# Sheet1.net
KiCad netlist of a schematic drawn in Altium Designer
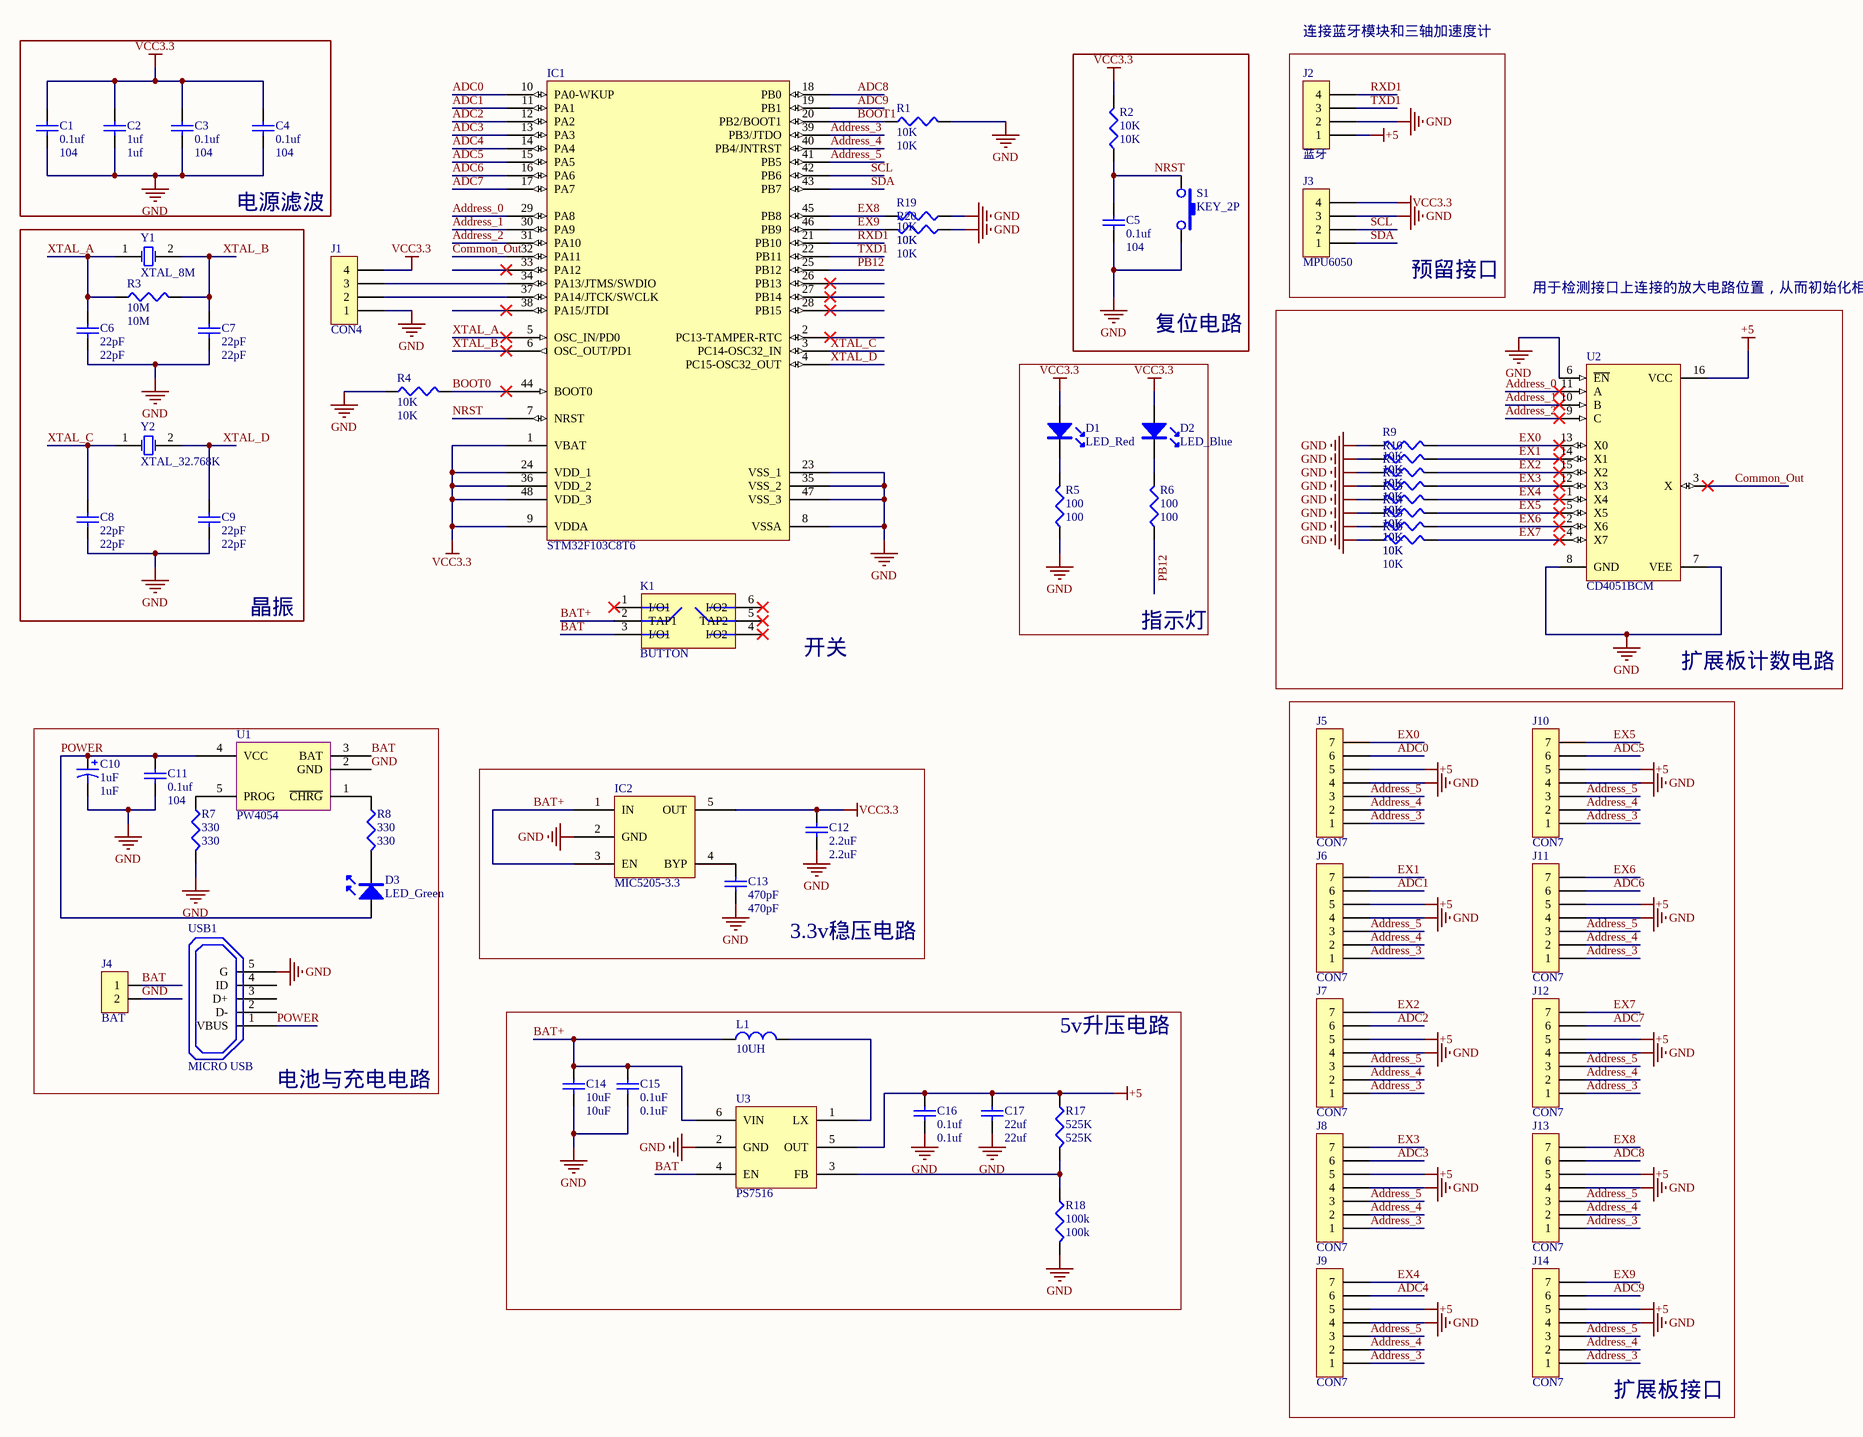
[diagram p0: Sheet1.SchDoc]

(export (version "E")
  (design (tool "Eeschema 10.0.6"))
  (components
    (comp (ref "C1")
      (value "0.1uf")
      (footprint "6-0805_L")
      (description "Capacitor (Semiconductor SIM Model)")
      (fields (field (name "ALTIUM_VALUE") "104") (field (name "PUBLISHER") "Altium Limited"))
      (libsource (lib "Miscellaneous Devices") (part "Cap Semi"))
    )
    (comp (ref "C2")
      (value "1uf")
      (footprint "6-0805_L")
      (description "Capacitor (Semiconductor SIM Model)")
      (fields (field (name "ALTIUM_VALUE") "1uf") (field (name "PUBLISHER") "Altium Limited"))
      (libsource (lib "Miscellaneous Devices") (part "Cap Semi"))
    )
    (comp (ref "C3")
      (value "0.1uf")
      (footprint "6-0805_L")
      (description "Capacitor (Semiconductor SIM Model)")
      (fields (field (name "ALTIUM_VALUE") "104") (field (name "PUBLISHER") "Altium Limited"))
      (libsource (lib "Miscellaneous Devices") (part "Cap Semi"))
    )
    (comp (ref "C4")
      (value "0.1uf")
      (footprint "6-0805_L")
      (description "Capacitor (Semiconductor SIM Model)")
      (fields (field (name "ALTIUM_VALUE") "104") (field (name "PUBLISHER") "Altium Limited"))
      (libsource (lib "Miscellaneous Devices") (part "Cap Semi"))
    )
    (comp (ref "C5")
      (value "0.1uf")
      (footprint "6-0805_L")
      (description "Capacitor (Semiconductor SIM Model)")
      (fields (field (name "ALTIUM_VALUE") "104") (field (name "PUBLISHER") "Altium Limited"))
      (libsource (lib "Miscellaneous Devices") (part "Cap Semi"))
    )
    (comp (ref "C6")
      (value "22pF")
      (footprint "6-0805_L")
      (description "Capacitor (Semiconductor SIM Model)")
      (fields (field (name "ALTIUM_VALUE") "22pF") (field (name "PUBLISHER") "Altium Limited"))
      (libsource (lib "Miscellaneous Devices") (part "Cap Semi"))
    )
    (comp (ref "C7")
      (value "22pF")
      (footprint "6-0805_L")
      (description "Capacitor (Semiconductor SIM Model)")
      (fields (field (name "ALTIUM_VALUE") "22pF") (field (name "PUBLISHER") "Altium Limited"))
      (libsource (lib "Miscellaneous Devices") (part "Cap Semi"))
    )
    (comp (ref "C8")
      (value "22pF")
      (footprint "6-0805_L")
      (description "Capacitor (Semiconductor SIM Model)")
      (fields (field (name "ALTIUM_VALUE") "22pF") (field (name "PUBLISHER") "Altium Limited"))
      (libsource (lib "Miscellaneous Devices") (part "Cap Semi"))
    )
    (comp (ref "C9")
      (value "22pF")
      (footprint "6-0805_L")
      (description "Capacitor (Semiconductor SIM Model)")
      (fields (field (name "ALTIUM_VALUE") "22pF") (field (name "PUBLISHER") "Altium Limited"))
      (libsource (lib "Miscellaneous Devices") (part "Cap Semi"))
    )
    (comp (ref "C10")
      (value "1uF")
      (footprint "C0805")
      (description "Polarized Capacitor (Surface Mount)")
      (fields (field (name "ALTIUM_VALUE") "1uF") (field (name "PUBLISHER") "Altium Limited"))
      (libsource (lib "Miscellaneous Devices") (part "Cap Pol3"))
    )
    (comp (ref "C11")
      (value "0.1uf")
      (footprint "6-0805_L")
      (description "Capacitor (Semiconductor SIM Model)")
      (fields (field (name "ALTIUM_VALUE") "104") (field (name "PUBLISHER") "Altium Limited"))
      (libsource (lib "Miscellaneous Devices") (part "Cap Semi"))
    )
    (comp (ref "C12")
      (value "2.2uF")
      (footprint "6-0805_L")
      (description "Capacitor (Semiconductor SIM Model)")
      (fields (field (name "ALTIUM_VALUE") "2.2uF") (field (name "PUBLISHER") "Altium Limited"))
      (libsource (lib "Miscellaneous Devices") (part "Cap Semi"))
    )
    (comp (ref "C13")
      (value "470pF")
      (footprint "6-0805_L")
      (description "Capacitor (Semiconductor SIM Model)")
      (fields (field (name "ALTIUM_VALUE") "470pF") (field (name "PUBLISHER") "Altium Limited"))
      (libsource (lib "Miscellaneous Devices") (part "Cap Semi"))
    )
    (comp (ref "C14")
      (value "10uF")
      (footprint "6-0805_L")
      (description "Capacitor (Semiconductor SIM Model)")
      (fields (field (name "ALTIUM_VALUE") "10uF") (field (name "PUBLISHER") "Altium Limited"))
      (libsource (lib "Miscellaneous Devices") (part "Cap Semi"))
    )
    (comp (ref "C15")
      (value "0.1uF")
      (footprint "6-0805_L")
      (description "Capacitor (Semiconductor SIM Model)")
      (fields (field (name "ALTIUM_VALUE") "0.1uF") (field (name "PUBLISHER") "Altium Limited"))
      (libsource (lib "Miscellaneous Devices") (part "Cap Semi"))
    )
    (comp (ref "C16")
      (value "0.1uf")
      (footprint "6-0805_L")
      (description "Capacitor (Semiconductor SIM Model)")
      (fields (field (name "ALTIUM_VALUE") "0.1uf") (field (name "PUBLISHER") "Altium Limited"))
      (libsource (lib "Miscellaneous Devices") (part "Cap Semi"))
    )
    (comp (ref "C17")
      (value "22uf")
      (footprint "6-0805_L")
      (description "Capacitor (Semiconductor SIM Model)")
      (fields (field (name "ALTIUM_VALUE") "22uf") (field (name "PUBLISHER") "Altium Limited"))
      (libsource (lib "Miscellaneous Devices") (part "Cap Semi"))
    )
    (comp (ref "D1")
      (value "LED_Red")
      (footprint "6-0805_M")
      (description "LED")
      (libsource (lib "Component") (part "LED"))
    )
    (comp (ref "D2")
      (value "LED_Blue")
      (footprint "6-0805_M")
      (description "LED")
      (libsource (lib "Component") (part "LED"))
    )
    (comp (ref "D3")
      (value "LED_Green")
      (footprint "6-0805_M")
      (description "LED")
      (libsource (lib "Component") (part "LED"))
    )
    (comp (ref "IC1")
      (value "STM32F103C8T6")
      (footprint "LQFP48")
      (description "单片机")
      (fields (field (name "PUBLISHER") "Altium Limited"))
      (libsource (lib "Chip") (part "STM32F103C8T6"))
    )
    (comp (ref "IC2")
      (value "MIC5205-3.3")
      (footprint "SOT-23-5")
      (description "稳压")
      (libsource (lib "Chip") (part "MIC5205-3.3"))
    )
    (comp (ref "J1")
      (value "CON4")
      (footprint "HDR1X4")
      (description "连接器")
      (libsource (lib "Connector") (part "CON4"))
    )
    (comp (ref "J2")
      (value "蓝牙")
      (footprint "HDR1X4")
      (description "Connector")
      (libsource (lib "杂元件库") (part "CON4"))
    )
    (comp (ref "J3")
      (value "MPU6050")
      (footprint "HDR1X4")
      (description "Connector")
      (libsource (lib "杂元件库") (part "CON4"))
    )
    (comp (ref "J4")
      (value "BAT")
      (footprint "HDR1X2")
      (description "Conjunctor")
      (libsource (lib "zj") (part "CON2"))
    )
    (comp (ref "J5")
      (value "CON7")
      (footprint "HDR1X7")
      (description "Connector")
      (libsource (lib "杂元件库") (part "CON7"))
    )
    (comp (ref "J6")
      (value "CON7")
      (footprint "HDR1X7")
      (description "Connector")
      (libsource (lib "杂元件库") (part "CON7"))
    )
    (comp (ref "J7")
      (value "CON7")
      (footprint "HDR1X7")
      (description "Connector")
      (libsource (lib "杂元件库") (part "CON7"))
    )
    (comp (ref "J8")
      (value "CON7")
      (footprint "HDR1X7")
      (description "Connector")
      (libsource (lib "杂元件库") (part "CON7"))
    )
    (comp (ref "J9")
      (value "CON7")
      (footprint "HDR1X7")
      (description "Connector")
      (libsource (lib "杂元件库") (part "CON7"))
    )
    (comp (ref "J10")
      (value "CON7")
      (footprint "HDR1X7")
      (description "Connector")
      (libsource (lib "杂元件库") (part "CON7"))
    )
    (comp (ref "J11")
      (value "CON7")
      (footprint "HDR1X7")
      (description "Connector")
      (libsource (lib "杂元件库") (part "CON7"))
    )
    (comp (ref "J12")
      (value "CON7")
      (footprint "HDR1X7")
      (description "Connector")
      (libsource (lib "杂元件库") (part "CON7"))
    )
    (comp (ref "J13")
      (value "CON7")
      (footprint "HDR1X7")
      (description "Connector")
      (libsource (lib "杂元件库") (part "CON7"))
    )
    (comp (ref "J14")
      (value "CON7")
      (footprint "HDR1X7")
      (description "Connector")
      (libsource (lib "杂元件库") (part "CON7"))
    )
    (comp (ref "K1")
      (value "BUTTON")
      (footprint "My:switch")
      (description "自锁按键")
      (libsource (lib "Component") (part "BUTTON"))
    )
    (comp (ref "L1")
      (value "10UH")
      (footprint "0850")
      (description "电感")
      (libsource (lib "Component") (part "Inductor"))
    )
    (comp (ref "R1")
      (value "10K")
      (footprint "6-0805_L")
      (description "Resistor")
      (fields (field (name "ALTIUM_VALUE") "10K") (field (name "PUBLISHER") "Altium Limited"))
      (libsource (lib "Miscellaneous Devices") (part "Res3"))
    )
    (comp (ref "R2")
      (value "10K")
      (footprint "6-0805_L")
      (description "Resistor")
      (fields (field (name "ALTIUM_VALUE") "10K") (field (name "PUBLISHER") "Altium Limited"))
      (libsource (lib "Miscellaneous Devices") (part "Res3"))
    )
    (comp (ref "R3")
      (value "10M")
      (footprint "6-0805_L")
      (description "Resistor")
      (fields (field (name "ALTIUM_VALUE") "10M") (field (name "PUBLISHER") "Altium Limited"))
      (libsource (lib "Miscellaneous Devices") (part "Res3"))
    )
    (comp (ref "R4")
      (value "10K")
      (footprint "6-0805_L")
      (description "Resistor")
      (fields (field (name "ALTIUM_VALUE") "10K") (field (name "PUBLISHER") "Altium Limited"))
      (libsource (lib "Miscellaneous Devices") (part "Res3"))
    )
    (comp (ref "R5")
      (value "100")
      (footprint "6-0805_L")
      (description "Resistor")
      (fields (field (name "ALTIUM_VALUE") "100") (field (name "PUBLISHER") "Altium Limited"))
      (libsource (lib "Miscellaneous Devices") (part "Res3"))
    )
    (comp (ref "R6")
      (value "100")
      (footprint "6-0805_L")
      (description "Resistor")
      (fields (field (name "ALTIUM_VALUE") "100") (field (name "PUBLISHER") "Altium Limited"))
      (libsource (lib "Miscellaneous Devices") (part "Res3"))
    )
    (comp (ref "R7")
      (value "330")
      (footprint "6-0805_L")
      (description "Resistor")
      (fields (field (name "ALTIUM_VALUE") "330") (field (name "PUBLISHER") "Altium Limited"))
      (libsource (lib "Miscellaneous Devices") (part "Res3"))
    )
    (comp (ref "R8")
      (value "330")
      (footprint "6-0805_L")
      (description "Resistor")
      (fields (field (name "ALTIUM_VALUE") "330") (field (name "PUBLISHER") "Altium Limited"))
      (libsource (lib "Miscellaneous Devices") (part "Res3"))
    )
    (comp (ref "R9")
      (value "10K")
      (footprint "6-0805_L")
      (description "Resistor")
      (fields (field (name "ALTIUM_VALUE") "10K") (field (name "PUBLISHER") "Altium Limited"))
      (libsource (lib "Miscellaneous Devices") (part "Res3"))
    )
    (comp (ref "R10")
      (value "10K")
      (footprint "6-0805_L")
      (description "Resistor")
      (fields (field (name "ALTIUM_VALUE") "10K") (field (name "PUBLISHER") "Altium Limited"))
      (libsource (lib "Miscellaneous Devices") (part "Res3"))
    )
    (comp (ref "R11")
      (value "10K")
      (footprint "6-0805_L")
      (description "Resistor")
      (fields (field (name "ALTIUM_VALUE") "10K") (field (name "PUBLISHER") "Altium Limited"))
      (libsource (lib "Miscellaneous Devices") (part "Res3"))
    )
    (comp (ref "R12")
      (value "10K")
      (footprint "6-0805_L")
      (description "Resistor")
      (fields (field (name "ALTIUM_VALUE") "10K") (field (name "PUBLISHER") "Altium Limited"))
      (libsource (lib "Miscellaneous Devices") (part "Res3"))
    )
    (comp (ref "R13")
      (value "10K")
      (footprint "6-0805_L")
      (description "Resistor")
      (fields (field (name "ALTIUM_VALUE") "10K") (field (name "PUBLISHER") "Altium Limited"))
      (libsource (lib "Miscellaneous Devices") (part "Res3"))
    )
    (comp (ref "R14")
      (value "10K")
      (footprint "6-0805_L")
      (description "Resistor")
      (fields (field (name "ALTIUM_VALUE") "10K") (field (name "PUBLISHER") "Altium Limited"))
      (libsource (lib "Miscellaneous Devices") (part "Res3"))
    )
    (comp (ref "R15")
      (value "10K")
      (footprint "6-0805_L")
      (description "Resistor")
      (fields (field (name "ALTIUM_VALUE") "10K") (field (name "PUBLISHER") "Altium Limited"))
      (libsource (lib "Miscellaneous Devices") (part "Res3"))
    )
    (comp (ref "R16")
      (value "10K")
      (footprint "6-0805_L")
      (description "Resistor")
      (fields (field (name "ALTIUM_VALUE") "10K") (field (name "PUBLISHER") "Altium Limited"))
      (libsource (lib "Miscellaneous Devices") (part "Res3"))
    )
    (comp (ref "R17")
      (value "525K")
      (footprint "6-0805_L")
      (description "Resistor")
      (fields (field (name "ALTIUM_VALUE") "525K") (field (name "PUBLISHER") "Altium Limited"))
      (libsource (lib "Miscellaneous Devices") (part "Res3"))
    )
    (comp (ref "R18")
      (value "100k")
      (footprint "6-0805_L")
      (description "Resistor")
      (fields (field (name "ALTIUM_VALUE") "100k") (field (name "PUBLISHER") "Altium Limited"))
      (libsource (lib "Miscellaneous Devices") (part "Res3"))
    )
    (comp (ref "R19")
      (value "10K")
      (footprint "6-0805_L")
      (description "Resistor")
      (fields (field (name "ALTIUM_VALUE") "10K") (field (name "PUBLISHER") "Altium Limited"))
      (libsource (lib "Miscellaneous Devices") (part "Res3"))
    )
    (comp (ref "R20")
      (value "10K")
      (footprint "6-0805_L")
      (description "Resistor")
      (fields (field (name "ALTIUM_VALUE") "10K") (field (name "PUBLISHER") "Altium Limited"))
      (libsource (lib "Miscellaneous Devices") (part "Res3"))
    )
    (comp (ref "S1")
      (value "KEY_2P")
      (footprint "My:button")
      (description "轻触按键2P")
      (libsource (lib "Component") (part "KEY_2P"))
    )
    (comp (ref "U1") (value "PW4054") (footprint "SOT-23-CT5_L") (libsource (lib "Schlib") (part "PW4054")))
    (comp (ref "U2")
      (value "CD4051BCM")
      (footprint "M16A_N")
      (description "8-Channel Analog Multiplexer/Demultiplexer")
      (fields (field (name "PUBLISHER") "Altium Limited"))
      (libsource (lib "altium-import") (part "root_0_CD4051BCM_"))
    )
    (comp (ref "U3")
      (value "PS7516")
      (footprint "SOT23-6_M")
      (libsource (lib "Integrated_Library1") (part "PS7516"))
    )
    (comp (ref "USB1")
      (value "MICRO USB")
      (footprint "MICRO USB")
      (libsource (lib "Connector") (part "MICRO USB"))
    )
    (comp (ref "Y1")
      (value "XTAL_8M")
      (footprint "xtal")
      (description "Crystal Oscillator")
      (fields (field (name "PUBLISHER") "Altium Limited"))
      (libsource (lib "Miscellaneous Devices") (part "XTAL"))
    )
    (comp (ref "Y2")
      (value "XTAL_32.768K")
      (footprint "R38")
      (description "Crystal Oscillator")
      (fields (field (name "PUBLISHER") "Altium Limited"))
      (libsource (lib "Miscellaneous Devices") (part "XTAL"))
    )
  )
  (nets
    (net (code "1") (name "+5") (class "Default")
      (node (ref "C16") (pin "2") (pinfunction "2_2") (pintype "passive"))
      (node (ref "C17") (pin "2") (pinfunction "2_2") (pintype "passive"))
      (node (ref "J10") (pin "5") (pinfunction "5_5") (pintype "passive"))
      (node (ref "J11") (pin "5") (pinfunction "5_5") (pintype "passive"))
      (node (ref "J12") (pin "5") (pinfunction "5_5") (pintype "passive"))
      (node (ref "J13") (pin "5") (pinfunction "5_5") (pintype "passive"))
      (node (ref "J14") (pin "5") (pinfunction "5_5") (pintype "passive"))
      (node (ref "J2") (pin "1") (pinfunction "1_1") (pintype "passive"))
      (node (ref "J5") (pin "5") (pinfunction "5_5") (pintype "passive"))
      (node (ref "J6") (pin "5") (pinfunction "5_5") (pintype "passive"))
      (node (ref "J7") (pin "5") (pinfunction "5_5") (pintype "passive"))
      (node (ref "J8") (pin "5") (pinfunction "5_5") (pintype "passive"))
      (node (ref "J9") (pin "5") (pinfunction "5_5") (pintype "passive"))
      (node (ref "R17") (pin "1") (pinfunction "1_1") (pintype "passive"))
      (node (ref "U2") (pin "16") (pinfunction "VCC_16") (pintype "power_in"))
      (node (ref "U3") (pin "5") (pinfunction "OUT_5") (pintype "passive"))
    )
    (net (code "2") (name "/ADC0") (class "Default")
      (node (ref "IC1") (pin "10") (pinfunction "PA0-WKUP_10") (pintype "bidirectional"))
      (node (ref "J5") (pin "6") (pinfunction "6_6") (pintype "passive"))
    )
    (net (code "3") (name "/ADC1") (class "Default")
      (node (ref "IC1") (pin "11") (pinfunction "PA1_11") (pintype "bidirectional"))
      (node (ref "J6") (pin "6") (pinfunction "6_6") (pintype "passive"))
    )
    (net (code "4") (name "/ADC2") (class "Default")
      (node (ref "IC1") (pin "12") (pinfunction "PA2_12") (pintype "bidirectional"))
      (node (ref "J7") (pin "6") (pinfunction "6_6") (pintype "passive"))
    )
    (net (code "5") (name "/ADC3") (class "Default")
      (node (ref "IC1") (pin "13") (pinfunction "PA3_13") (pintype "bidirectional"))
      (node (ref "J8") (pin "6") (pinfunction "6_6") (pintype "passive"))
    )
    (net (code "6") (name "/ADC4") (class "Default")
      (node (ref "IC1") (pin "14") (pinfunction "PA4_14") (pintype "bidirectional"))
      (node (ref "J9") (pin "6") (pinfunction "6_6") (pintype "passive"))
    )
    (net (code "7") (name "/ADC5") (class "Default")
      (node (ref "IC1") (pin "15") (pinfunction "PA5_15") (pintype "bidirectional"))
      (node (ref "J10") (pin "6") (pinfunction "6_6") (pintype "passive"))
    )
    (net (code "8") (name "/ADC6") (class "Default")
      (node (ref "IC1") (pin "16") (pinfunction "PA6_16") (pintype "bidirectional"))
      (node (ref "J11") (pin "6") (pinfunction "6_6") (pintype "passive"))
    )
    (net (code "9") (name "/ADC7") (class "Default")
      (node (ref "IC1") (pin "17") (pinfunction "PA7_17") (pintype "bidirectional"))
      (node (ref "J12") (pin "6") (pinfunction "6_6") (pintype "passive"))
    )
    (net (code "10") (name "/ADC8") (class "Default")
      (node (ref "IC1") (pin "18") (pinfunction "PB0_18") (pintype "bidirectional"))
      (node (ref "J13") (pin "6") (pinfunction "6_6") (pintype "passive"))
    )
    (net (code "11") (name "/ADC9") (class "Default")
      (node (ref "IC1") (pin "19") (pinfunction "PB1_19") (pintype "bidirectional"))
      (node (ref "J14") (pin "6") (pinfunction "6_6") (pintype "passive"))
    )
    (net (code "12") (name "/Address_0") (class "Default")
      (node (ref "IC1") (pin "29") (pinfunction "PA8_29") (pintype "bidirectional"))
      (node (ref "U2") (pin "11") (pinfunction "A_11") (pintype "input"))
    )
    (net (code "13") (name "/Address_1") (class "Default")
      (node (ref "IC1") (pin "30") (pinfunction "PA9_30") (pintype "bidirectional"))
      (node (ref "U2") (pin "10") (pinfunction "B_10") (pintype "input"))
    )
    (net (code "14") (name "/Address_2") (class "Default")
      (node (ref "IC1") (pin "31") (pinfunction "PA10_31") (pintype "bidirectional"))
      (node (ref "U2") (pin "9") (pinfunction "C_9") (pintype "input"))
    )
    (net (code "15") (name "/Address_3") (class "Default")
      (node (ref "IC1") (pin "39") (pinfunction "PB3/JTDO_39") (pintype "bidirectional"))
      (node (ref "J10") (pin "1") (pinfunction "1_1") (pintype "passive"))
      (node (ref "J11") (pin "1") (pinfunction "1_1") (pintype "passive"))
      (node (ref "J12") (pin "1") (pinfunction "1_1") (pintype "passive"))
      (node (ref "J13") (pin "1") (pinfunction "1_1") (pintype "passive"))
      (node (ref "J14") (pin "1") (pinfunction "1_1") (pintype "passive"))
      (node (ref "J5") (pin "1") (pinfunction "1_1") (pintype "passive"))
      (node (ref "J6") (pin "1") (pinfunction "1_1") (pintype "passive"))
      (node (ref "J7") (pin "1") (pinfunction "1_1") (pintype "passive"))
      (node (ref "J8") (pin "1") (pinfunction "1_1") (pintype "passive"))
      (node (ref "J9") (pin "1") (pinfunction "1_1") (pintype "passive"))
    )
    (net (code "16") (name "/Address_4") (class "Default")
      (node (ref "IC1") (pin "40") (pinfunction "PB4/JNTRST_40") (pintype "bidirectional"))
      (node (ref "J10") (pin "2") (pinfunction "2_2") (pintype "passive"))
      (node (ref "J11") (pin "2") (pinfunction "2_2") (pintype "passive"))
      (node (ref "J12") (pin "2") (pinfunction "2_2") (pintype "passive"))
      (node (ref "J13") (pin "2") (pinfunction "2_2") (pintype "passive"))
      (node (ref "J14") (pin "2") (pinfunction "2_2") (pintype "passive"))
      (node (ref "J5") (pin "2") (pinfunction "2_2") (pintype "passive"))
      (node (ref "J6") (pin "2") (pinfunction "2_2") (pintype "passive"))
      (node (ref "J7") (pin "2") (pinfunction "2_2") (pintype "passive"))
      (node (ref "J8") (pin "2") (pinfunction "2_2") (pintype "passive"))
      (node (ref "J9") (pin "2") (pinfunction "2_2") (pintype "passive"))
    )
    (net (code "17") (name "/Address_5") (class "Default")
      (node (ref "IC1") (pin "41") (pinfunction "PB5_41") (pintype "bidirectional"))
      (node (ref "J10") (pin "3") (pinfunction "3_3") (pintype "passive"))
      (node (ref "J11") (pin "3") (pinfunction "3_3") (pintype "passive"))
      (node (ref "J12") (pin "3") (pinfunction "3_3") (pintype "passive"))
      (node (ref "J13") (pin "3") (pinfunction "3_3") (pintype "passive"))
      (node (ref "J14") (pin "3") (pinfunction "3_3") (pintype "passive"))
      (node (ref "J5") (pin "3") (pinfunction "3_3") (pintype "passive"))
      (node (ref "J6") (pin "3") (pinfunction "3_3") (pintype "passive"))
      (node (ref "J7") (pin "3") (pinfunction "3_3") (pintype "passive"))
      (node (ref "J8") (pin "3") (pinfunction "3_3") (pintype "passive"))
      (node (ref "J9") (pin "3") (pinfunction "3_3") (pintype "passive"))
    )
    (net (code "18") (name "/BAT") (class "Default")
      (node (ref "J4") (pin "1") (pinfunction "1_1") (pintype "passive"))
      (node (ref "K1") (pin "3") (pinfunction "I/O1_3") (pintype "passive"))
      (node (ref "U1") (pin "3") (pinfunction "BAT_3") (pintype "passive"))
      (node (ref "U3") (pin "4") (pinfunction "EN_4") (pintype "passive"))
    )
    (net (code "19") (name "/BAT+") (class "Default")
      (node (ref "C14") (pin "2") (pinfunction "2_2") (pintype "passive"))
      (node (ref "C15") (pin "2") (pinfunction "2_2") (pintype "passive"))
      (node (ref "IC2") (pin "1") (pinfunction "IN_1") (pintype "passive"))
      (node (ref "IC2") (pin "3") (pinfunction "EN_3") (pintype "passive"))
      (node (ref "K1") (pin "2") (pinfunction "TAP1_2") (pintype "passive"))
      (node (ref "L1") (pin "1") (pinfunction "1_1") (pintype "passive"))
      (node (ref "U3") (pin "6") (pinfunction "VIN_6") (pintype "passive"))
    )
    (net (code "20") (name "/BOOT0") (class "Default")
      (node (ref "IC1") (pin "44") (pinfunction "BOOT0_44") (pintype "input"))
      (node (ref "R4") (pin "2") (pinfunction "2_2") (pintype "passive"))
    )
    (net (code "21") (name "/BOOT1") (class "Default")
      (node (ref "IC1") (pin "20") (pinfunction "PB2/BOOT1_20") (pintype "bidirectional"))
      (node (ref "R1") (pin "1") (pinfunction "1_1") (pintype "passive"))
    )
    (net (code "22") (name "/Common_Out") (class "Default")
      (node (ref "IC1") (pin "32") (pinfunction "PA11_32") (pintype "bidirectional"))
      (node (ref "U2") (pin "3") (pinfunction "X_3") (pintype "bidirectional"))
    )
    (net (code "23") (name "/EX0") (class "Default")
      (node (ref "J5") (pin "7") (pinfunction "7_7") (pintype "passive"))
      (node (ref "R9") (pin "2") (pinfunction "2_2") (pintype "passive"))
      (node (ref "U2") (pin "13") (pinfunction "X0_13") (pintype "bidirectional"))
    )
    (net (code "24") (name "/EX1") (class "Default")
      (node (ref "J6") (pin "7") (pinfunction "7_7") (pintype "passive"))
      (node (ref "R10") (pin "2") (pinfunction "2_2") (pintype "passive"))
      (node (ref "U2") (pin "14") (pinfunction "X1_14") (pintype "bidirectional"))
    )
    (net (code "25") (name "/EX2") (class "Default")
      (node (ref "J7") (pin "7") (pinfunction "7_7") (pintype "passive"))
      (node (ref "R11") (pin "2") (pinfunction "2_2") (pintype "passive"))
      (node (ref "U2") (pin "15") (pinfunction "X2_15") (pintype "bidirectional"))
    )
    (net (code "26") (name "/EX3") (class "Default")
      (node (ref "J8") (pin "7") (pinfunction "7_7") (pintype "passive"))
      (node (ref "R12") (pin "2") (pinfunction "2_2") (pintype "passive"))
      (node (ref "U2") (pin "12") (pinfunction "X3_12") (pintype "bidirectional"))
    )
    (net (code "27") (name "/EX4") (class "Default")
      (node (ref "J9") (pin "7") (pinfunction "7_7") (pintype "passive"))
      (node (ref "R13") (pin "2") (pinfunction "2_2") (pintype "passive"))
      (node (ref "U2") (pin "1") (pinfunction "X4_1") (pintype "bidirectional"))
    )
    (net (code "28") (name "/EX5") (class "Default")
      (node (ref "J10") (pin "7") (pinfunction "7_7") (pintype "passive"))
      (node (ref "R14") (pin "2") (pinfunction "2_2") (pintype "passive"))
      (node (ref "U2") (pin "5") (pinfunction "X5_5") (pintype "bidirectional"))
    )
    (net (code "29") (name "/EX6") (class "Default")
      (node (ref "J11") (pin "7") (pinfunction "7_7") (pintype "passive"))
      (node (ref "R15") (pin "2") (pinfunction "2_2") (pintype "passive"))
      (node (ref "U2") (pin "2") (pinfunction "X6_2") (pintype "bidirectional"))
    )
    (net (code "30") (name "/EX7") (class "Default")
      (node (ref "J12") (pin "7") (pinfunction "7_7") (pintype "passive"))
      (node (ref "R16") (pin "2") (pinfunction "2_2") (pintype "passive"))
      (node (ref "U2") (pin "4") (pinfunction "X7_4") (pintype "bidirectional"))
    )
    (net (code "31") (name "/EX8") (class "Default")
      (node (ref "IC1") (pin "45") (pinfunction "PB8_45") (pintype "bidirectional"))
      (node (ref "J13") (pin "7") (pinfunction "7_7") (pintype "passive"))
      (node (ref "R19") (pin "2") (pinfunction "2_2") (pintype "passive"))
    )
    (net (code "32") (name "/EX9") (class "Default")
      (node (ref "IC1") (pin "46") (pinfunction "PB9_46") (pintype "bidirectional"))
      (node (ref "J14") (pin "7") (pinfunction "7_7") (pintype "passive"))
      (node (ref "R20") (pin "2") (pinfunction "2_2") (pintype "passive"))
    )
    (net (code "33") (name "/NRST") (class "Default")
      (node (ref "C5") (pin "2") (pinfunction "2_2") (pintype "passive"))
      (node (ref "IC1") (pin "7") (pinfunction "NRST_7") (pintype "bidirectional"))
      (node (ref "R2") (pin "1") (pinfunction "1_1") (pintype "passive"))
      (node (ref "S1") (pin "1") (pinfunction "1_1") (pintype "passive"))
    )
    (net (code "34") (name "/PB12") (class "Default")
      (node (ref "IC1") (pin "25") (pinfunction "PB12_25") (pintype "bidirectional"))
      (node (ref "R6") (pin "1") (pinfunction "1_1") (pintype "passive"))
    )
    (net (code "35") (name "/POWER") (class "Default")
      (node (ref "C10") (pin "1") (pinfunction "1_1") (pintype "passive"))
      (node (ref "C11") (pin "2") (pinfunction "2_2") (pintype "passive"))
      (node (ref "D3") (pin "1") (pinfunction "1_1") (pintype "passive"))
      (node (ref "U1") (pin "4") (pinfunction "VCC_4") (pintype "passive"))
      (node (ref "USB1") (pin "1") (pinfunction "VBUS_1") (pintype "passive"))
    )
    (net (code "36") (name "/RXD1") (class "Default")
      (node (ref "IC1") (pin "21") (pinfunction "PB10_21") (pintype "bidirectional"))
      (node (ref "J2") (pin "4") (pinfunction "4_4") (pintype "passive"))
    )
    (net (code "37") (name "/SCL") (class "Default")
      (node (ref "IC1") (pin "42") (pinfunction "PB6_42") (pintype "bidirectional"))
      (node (ref "J3") (pin "2") (pinfunction "2_2") (pintype "passive"))
    )
    (net (code "38") (name "/SDA") (class "Default")
      (node (ref "IC1") (pin "43") (pinfunction "PB7_43") (pintype "bidirectional"))
      (node (ref "J3") (pin "1") (pinfunction "1_1") (pintype "passive"))
    )
    (net (code "39") (name "/TXD1") (class "Default")
      (node (ref "IC1") (pin "22") (pinfunction "PB11_22") (pintype "bidirectional"))
      (node (ref "J2") (pin "3") (pinfunction "3_3") (pintype "passive"))
    )
    (net (code "40") (name "/XTAL_A") (class "Default")
      (node (ref "C6") (pin "2") (pinfunction "2_2") (pintype "passive"))
      (node (ref "IC1") (pin "5") (pinfunction "OSC_IN/PD0_5") (pintype "input"))
      (node (ref "R3") (pin "1") (pinfunction "1_1") (pintype "passive"))
      (node (ref "Y1") (pin "1") (pinfunction "OSC1_1") (pintype "passive"))
    )
    (net (code "41") (name "/XTAL_B") (class "Default")
      (node (ref "C7") (pin "2") (pinfunction "2_2") (pintype "passive"))
      (node (ref "IC1") (pin "6") (pinfunction "OSC_OUT/PD1_6") (pintype "output"))
      (node (ref "R3") (pin "2") (pinfunction "2_2") (pintype "passive"))
      (node (ref "Y1") (pin "2") (pinfunction "OSC2_2") (pintype "passive"))
    )
    (net (code "42") (name "/XTAL_C") (class "Default")
      (node (ref "C8") (pin "2") (pinfunction "2_2") (pintype "passive"))
      (node (ref "IC1") (pin "3") (pinfunction "PC14-OSC32_IN_3") (pintype "bidirectional"))
      (node (ref "Y2") (pin "1") (pinfunction "OSC1_1") (pintype "passive"))
    )
    (net (code "43") (name "/XTAL_D") (class "Default")
      (node (ref "C9") (pin "2") (pinfunction "2_2") (pintype "passive"))
      (node (ref "IC1") (pin "4") (pinfunction "PC15-OSC32_OUT_4") (pintype "bidirectional"))
      (node (ref "Y2") (pin "2") (pinfunction "OSC2_2") (pintype "passive"))
    )
    (net (code "44") (name "GND") (class "Default")
      (node (ref "C1") (pin "1") (pinfunction "1_1") (pintype "passive"))
      (node (ref "C10") (pin "2") (pinfunction "2_2") (pintype "passive"))
      (node (ref "C11") (pin "1") (pinfunction "1_1") (pintype "passive"))
      (node (ref "C12") (pin "1") (pinfunction "1_1") (pintype "passive"))
      (node (ref "C13") (pin "1") (pinfunction "1_1") (pintype "passive"))
      (node (ref "C14") (pin "1") (pinfunction "1_1") (pintype "passive"))
      (node (ref "C15") (pin "1") (pinfunction "1_1") (pintype "passive"))
      (node (ref "C16") (pin "1") (pinfunction "1_1") (pintype "passive"))
      (node (ref "C17") (pin "1") (pinfunction "1_1") (pintype "passive"))
      (node (ref "C2") (pin "1") (pinfunction "1_1") (pintype "passive"))
      (node (ref "C3") (pin "1") (pinfunction "1_1") (pintype "passive"))
      (node (ref "C4") (pin "1") (pinfunction "1_1") (pintype "passive"))
      (node (ref "C5") (pin "1") (pinfunction "1_1") (pintype "passive"))
      (node (ref "C6") (pin "1") (pinfunction "1_1") (pintype "passive"))
      (node (ref "C7") (pin "1") (pinfunction "1_1") (pintype "passive"))
      (node (ref "C8") (pin "1") (pinfunction "1_1") (pintype "passive"))
      (node (ref "C9") (pin "1") (pinfunction "1_1") (pintype "passive"))
      (node (ref "IC1") (pin "23") (pinfunction "VSS_1_23") (pintype "power_in"))
      (node (ref "IC1") (pin "35") (pinfunction "VSS_2_35") (pintype "power_in"))
      (node (ref "IC1") (pin "47") (pinfunction "VSS_3_47") (pintype "power_in"))
      (node (ref "IC1") (pin "8") (pinfunction "VSSA_8") (pintype "power_in"))
      (node (ref "IC2") (pin "2") (pinfunction "GND_2") (pintype "passive"))
      (node (ref "J1") (pin "1") (pinfunction "1_1") (pintype "passive"))
      (node (ref "J10") (pin "4") (pinfunction "4_4") (pintype "passive"))
      (node (ref "J11") (pin "4") (pinfunction "4_4") (pintype "passive"))
      (node (ref "J12") (pin "4") (pinfunction "4_4") (pintype "passive"))
      (node (ref "J13") (pin "4") (pinfunction "4_4") (pintype "passive"))
      (node (ref "J14") (pin "4") (pinfunction "4_4") (pintype "passive"))
      (node (ref "J2") (pin "2") (pinfunction "2_2") (pintype "passive"))
      (node (ref "J3") (pin "3") (pinfunction "3_3") (pintype "passive"))
      (node (ref "J4") (pin "2") (pinfunction "2_2") (pintype "passive"))
      (node (ref "J5") (pin "4") (pinfunction "4_4") (pintype "passive"))
      (node (ref "J6") (pin "4") (pinfunction "4_4") (pintype "passive"))
      (node (ref "J7") (pin "4") (pinfunction "4_4") (pintype "passive"))
      (node (ref "J8") (pin "4") (pinfunction "4_4") (pintype "passive"))
      (node (ref "J9") (pin "4") (pinfunction "4_4") (pintype "passive"))
      (node (ref "R1") (pin "2") (pinfunction "2_2") (pintype "passive"))
      (node (ref "R10") (pin "1") (pinfunction "1_1") (pintype "passive"))
      (node (ref "R11") (pin "1") (pinfunction "1_1") (pintype "passive"))
      (node (ref "R12") (pin "1") (pinfunction "1_1") (pintype "passive"))
      (node (ref "R13") (pin "1") (pinfunction "1_1") (pintype "passive"))
      (node (ref "R14") (pin "1") (pinfunction "1_1") (pintype "passive"))
      (node (ref "R15") (pin "1") (pinfunction "1_1") (pintype "passive"))
      (node (ref "R16") (pin "1") (pinfunction "1_1") (pintype "passive"))
      (node (ref "R18") (pin "2") (pinfunction "2_2") (pintype "passive"))
      (node (ref "R19") (pin "1") (pinfunction "1_1") (pintype "passive"))
      (node (ref "R20") (pin "1") (pinfunction "1_1") (pintype "passive"))
      (node (ref "R4") (pin "1") (pinfunction "1_1") (pintype "passive"))
      (node (ref "R5") (pin "1") (pinfunction "1_1") (pintype "passive"))
      (node (ref "R7") (pin "2") (pinfunction "2_2") (pintype "passive"))
      (node (ref "R9") (pin "1") (pinfunction "1_1") (pintype "passive"))
      (node (ref "S1") (pin "2") (pinfunction "2_2") (pintype "passive"))
      (node (ref "U1") (pin "2") (pinfunction "GND_2") (pintype "passive"))
      (node (ref "U2") (pin "6") (pinfunction "~{EN}_6") (pintype "input"))
      (node (ref "U2") (pin "7") (pinfunction "VEE_7") (pintype "power_in"))
      (node (ref "U2") (pin "8") (pinfunction "GND_8") (pintype "power_in"))
      (node (ref "U3") (pin "2") (pinfunction "GND_2") (pintype "passive"))
      (node (ref "USB1") (pin "5") (pinfunction "G_5") (pintype "passive"))
    )
    (net (code "45") (name "Net-(D1-Pad2)") (class "Default")
      (node (ref "D1") (pin "2") (pinfunction "2_2") (pintype "passive"))
      (node (ref "R5") (pin "2") (pinfunction "2_2") (pintype "passive"))
    )
    (net (code "46") (name "Net-(D2-Pad2)") (class "Default")
      (node (ref "D2") (pin "2") (pinfunction "2_2") (pintype "passive"))
      (node (ref "R6") (pin "2") (pinfunction "2_2") (pintype "passive"))
    )
    (net (code "47") (name "Net-(D3-Pad2)") (class "Default")
      (node (ref "D3") (pin "2") (pinfunction "2_2") (pintype "passive"))
      (node (ref "R8") (pin "2") (pinfunction "2_2") (pintype "passive"))
    )
    (net (code "48") (name "Net-(IC1-PA13{slash}JTMS{slash}SWDIO)") (class "Default")
      (node (ref "IC1") (pin "34") (pinfunction "PA13/JTMS/SWDIO_34") (pintype "bidirectional"))
      (node (ref "J1") (pin "3") (pinfunction "3_3") (pintype "passive"))
    )
    (net (code "49") (name "Net-(IC1-PA14{slash}JTCK{slash}SWCLK)") (class "Default")
      (node (ref "IC1") (pin "37") (pinfunction "PA14/JTCK/SWCLK_37") (pintype "bidirectional"))
      (node (ref "J1") (pin "2") (pinfunction "2_2") (pintype "passive"))
    )
    (net (code "50") (name "Net-(IC2-BYP)") (class "Default")
      (node (ref "C13") (pin "2") (pinfunction "2_2") (pintype "passive"))
      (node (ref "IC2") (pin "4") (pinfunction "BYP_4") (pintype "passive"))
    )
    (net (code "51") (name "Net-(U1-PROG)") (class "Default")
      (node (ref "R7") (pin "1") (pinfunction "1_1") (pintype "passive"))
      (node (ref "U1") (pin "5") (pinfunction "PROG_5") (pintype "passive"))
    )
    (net (code "52") (name "Net-(U1-~{CHRG})") (class "Default")
      (node (ref "R8") (pin "1") (pinfunction "1_1") (pintype "passive"))
      (node (ref "U1") (pin "1") (pinfunction "~{CHRG}_1") (pintype "passive"))
    )
    (net (code "53") (name "Net-(U3-FB)") (class "Default")
      (node (ref "R17") (pin "2") (pinfunction "2_2") (pintype "passive"))
      (node (ref "R18") (pin "1") (pinfunction "1_1") (pintype "passive"))
      (node (ref "U3") (pin "3") (pinfunction "FB_3") (pintype "passive"))
    )
    (net (code "54") (name "Net-(U3-LX)") (class "Default")
      (node (ref "L1") (pin "2") (pinfunction "2_2") (pintype "passive"))
      (node (ref "U3") (pin "1") (pinfunction "LX_1") (pintype "passive"))
    )
    (net (code "55") (name "VCC3.3") (class "Default")
      (node (ref "C1") (pin "2") (pinfunction "2_2") (pintype "passive"))
      (node (ref "C12") (pin "2") (pinfunction "2_2") (pintype "passive"))
      (node (ref "C2") (pin "2") (pinfunction "2_2") (pintype "passive"))
      (node (ref "C3") (pin "2") (pinfunction "2_2") (pintype "passive"))
      (node (ref "C4") (pin "2") (pinfunction "2_2") (pintype "passive"))
      (node (ref "D1") (pin "1") (pinfunction "1_1") (pintype "passive"))
      (node (ref "D2") (pin "1") (pinfunction "1_1") (pintype "passive"))
      (node (ref "IC1") (pin "1") (pinfunction "VBAT_1") (pintype "power_in"))
      (node (ref "IC1") (pin "24") (pinfunction "VDD_1_24") (pintype "power_in"))
      (node (ref "IC1") (pin "36") (pinfunction "VDD_2_36") (pintype "power_in"))
      (node (ref "IC1") (pin "48") (pinfunction "VDD_3_48") (pintype "power_in"))
      (node (ref "IC1") (pin "9") (pinfunction "VDDA_9") (pintype "power_in"))
      (node (ref "IC2") (pin "5") (pinfunction "OUT_5") (pintype "passive"))
      (node (ref "J1") (pin "4") (pinfunction "4_4") (pintype "passive"))
      (node (ref "J3") (pin "4") (pinfunction "4_4") (pintype "passive"))
      (node (ref "R2") (pin "2") (pinfunction "2_2") (pintype "passive"))
    )
    (net (code "56") (name "unconnected-(IC1-PA12-Pad33)") (class "Default")
      (node (ref "IC1") (pin "33") (pinfunction "PA12_33") (pintype "bidirectional+no_connect"))
    )
    (net (code "57") (name "unconnected-(IC1-PA15{slash}JTDI-Pad38)") (class "Default")
      (node (ref "IC1") (pin "38") (pinfunction "PA15/JTDI_38") (pintype "bidirectional+no_connect"))
    )
    (net (code "58") (name "unconnected-(IC1-PB13-Pad26)") (class "Default")
      (node (ref "IC1") (pin "26") (pinfunction "PB13_26") (pintype "bidirectional+no_connect"))
    )
    (net (code "59") (name "unconnected-(IC1-PB14-Pad27)") (class "Default")
      (node (ref "IC1") (pin "27") (pinfunction "PB14_27") (pintype "bidirectional+no_connect"))
    )
    (net (code "60") (name "unconnected-(IC1-PB15-Pad28)") (class "Default")
      (node (ref "IC1") (pin "28") (pinfunction "PB15_28") (pintype "bidirectional+no_connect"))
    )
    (net (code "61") (name "unconnected-(IC1-PC13-TAMPER-RTC-Pad2)") (class "Default")
      (node (ref "IC1") (pin "2") (pinfunction "PC13-TAMPER-RTC_2") (pintype "bidirectional+no_connect"))
    )
    (net (code "62") (name "unconnected-(K1-I{slash}O1-Pad1)") (class "Default")
      (node (ref "K1") (pin "1") (pinfunction "I/O1_1") (pintype "passive+no_connect"))
    )
    (net (code "63") (name "unconnected-(K1-I{slash}O2-Pad4)") (class "Default")
      (node (ref "K1") (pin "4") (pinfunction "I/O2_4") (pintype "passive+no_connect"))
    )
    (net (code "64") (name "unconnected-(K1-I{slash}O2-Pad6)") (class "Default")
      (node (ref "K1") (pin "6") (pinfunction "I/O2_6") (pintype "passive+no_connect"))
    )
    (net (code "65") (name "unconnected-(K1-TAP2-Pad5)") (class "Default")
      (node (ref "K1") (pin "5") (pinfunction "TAP2_5") (pintype "passive+no_connect"))
    )
    (net (code "66") (name "unconnected-(USB1-D+-Pad3)") (class "Default")
      (node (ref "USB1") (pin "3") (pinfunction "D+_3") (pintype "passive"))
    )
    (net (code "67") (name "unconnected-(USB1-D--Pad2)") (class "Default")
      (node (ref "USB1") (pin "2") (pinfunction "D-_2") (pintype "passive"))
    )
    (net (code "68") (name "unconnected-(USB1-ID-Pad4)") (class "Default")
      (node (ref "USB1") (pin "4") (pinfunction "ID_4") (pintype "passive"))
    )
  )
)
